# SixAx.net
KiCad netlist of a schematic drawn in Altium Designer
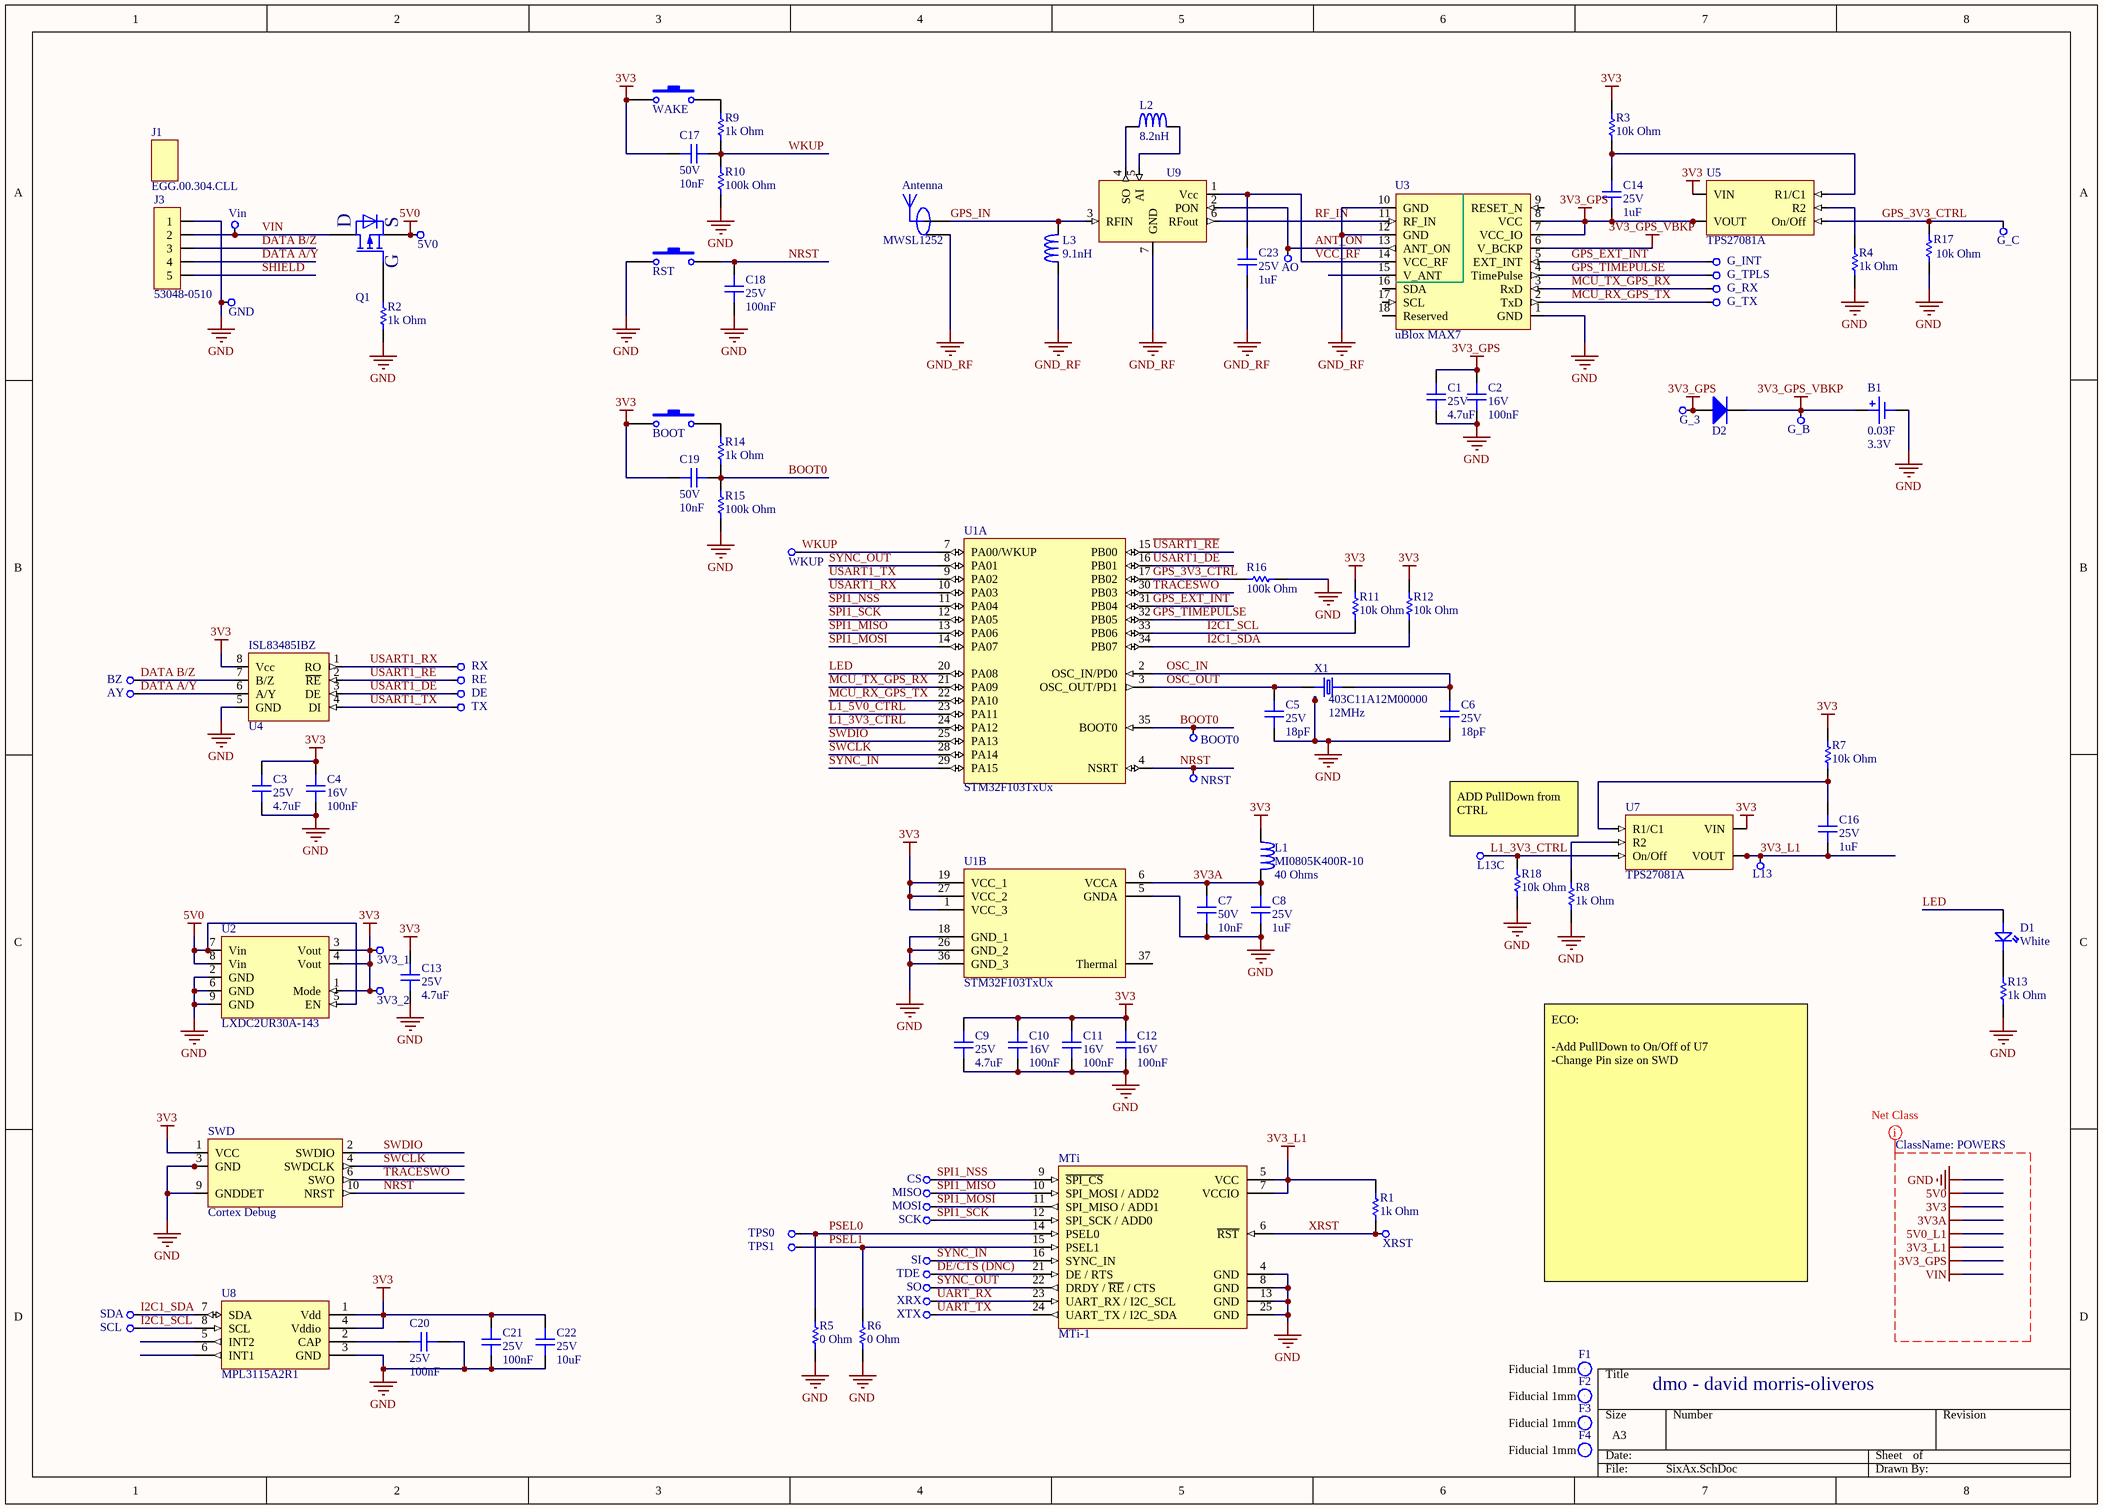
[diagram p0: SixAx.SchDoc]

(export (version "E")
  (design (tool "Eeschema 10.0.6"))
  (components
    (comp (ref "3V3_1")
      (value "TEST")
      (footprint "TEST_1.0mm, SMD")
      (libsource (lib "NaniBox_Conn") (part "TEST"))
    )
    (comp (ref "3V3_2")
      (value "TEST")
      (footprint "TEST_1.0mm, SMD")
      (libsource (lib "NaniBox_Conn") (part "TEST"))
    )
    (comp (ref "5V0")
      (value "TEST")
      (footprint "TEST_1.0mm, SMD")
      (libsource (lib "NaniBox_Conn") (part "TEST"))
    )
    (comp (ref "Antenna")
      (value "MWSL1252")
      (footprint "MWSL1252 - Vertical - SMALLER")
      (description "GPS Antenna, Passive, SMD")
      (fields (field (name "MANUFACTURER") "Maruwa"))
      (libsource (lib "NaniBox_Conn") (part "MWSL1252"))
    )
    (comp (ref "AO")
      (value "TEST")
      (footprint "TEST_0.5mm, SMD")
      (libsource (lib "NaniBox_Conn") (part "TEST"))
    )
    (comp (ref "AY")
      (value "TEST")
      (footprint "TEST_0.5mm, SMD")
      (libsource (lib "NaniBox_Conn") (part "TEST"))
    )
    (comp (ref "B1")
      (value "0.03F")
      (footprint "PAS409HR-VE5R")
      (description "Super Cap, 3.3V, 0.03F")
      (fields
        (field (name "MANUFACTURER") "Taiyo Yuden")
        (field (name "MANUFACTURER PART NUMBER") "PAS409HR-VE5R")
        (field (name "VOLTAGE") "3.3V")
      )
      (libsource (lib "NaniBox") (part "PAS409HR-VE5R"))
    )
    (comp (ref "BOOT")
      (value "TL1015AF160QG")
      (footprint "TL1015AF160QG")
      (description "Switch, Tactile, SMD")
      (fields (field (name "MANUFACTURER") "E-Switch"))
      (libsource (lib "NaniBox") (part "TL1015AF160QG"))
    )
    (comp (ref "BOOT0")
      (value "TEST")
      (footprint "TEST_0.5mm, SMD")
      (libsource (lib "NaniBox_Conn") (part "TEST"))
    )
    (comp (ref "BZ")
      (value "TEST")
      (footprint "TEST_0.5mm, SMD")
      (libsource (lib "NaniBox_Conn") (part "TEST"))
    )
    (comp (ref "C1")
      (value "4.7uF")
      (footprint "CAP 0805")
      (description "MLCC, 4.7uF, 0805, 10%, 25V, X5R")
      (fields
        (field (name "MANUFACTURER") "Samsung")
        (field (name "MANUFACTURER PART NUMBER") "CL21A475KAQNNNE")
        (field (name "VOLTAGE RATING") "25V")
      )
      (libsource (lib "NaniBox") (part "CL21A475KAQNNNE"))
    )
    (comp (ref "C2")
      (value "100nF")
      (footprint "CAP 0402")
      (description "MLCC, 100nF, 0402, 10%, 16V, X7R")
      (fields
        (field (name "MANUFACTURER") "Samsung")
        (field (name "MANUFACTURER PART NUMBER") "CL05B104KO5NNNC")
        (field (name "VOLTAGE RATING") "16V")
      )
      (libsource (lib "NaniBox") (part "CL05B104KO5NNNC"))
    )
    (comp (ref "C3")
      (value "4.7uF")
      (footprint "CAP 0805")
      (description "MLCC, 4.7uF, 0805, 10%, 25V, X5R")
      (fields
        (field (name "MANUFACTURER") "Samsung")
        (field (name "MANUFACTURER PART NUMBER") "CL21A475KAQNNNE")
        (field (name "VOLTAGE RATING") "25V")
      )
      (libsource (lib "NaniBox") (part "CL21A475KAQNNNE"))
    )
    (comp (ref "C4")
      (value "100nF")
      (footprint "CAP 0402")
      (description "MLCC, 100nF, 0402, 10%, 16V, X7R")
      (fields
        (field (name "MANUFACTURER") "Samsung")
        (field (name "MANUFACTURER PART NUMBER") "CL05B104KO5NNNC")
        (field (name "VOLTAGE RATING") "16V")
      )
      (libsource (lib "NaniBox") (part "CL05B104KO5NNNC"))
    )
    (comp (ref "C5")
      (value "18pF")
      (footprint "CAP 0402")
      (description "MLCC, 18pF, 0402, 5%, 25V, C0G")
      (fields
        (field (name "MANUFACTURER") "muRata")
        (field (name "MANUFACTURER PART NUMBER") "GRM1555C1E180JA01D")
        (field (name "VOLTAGE RATING") "25V")
      )
      (libsource (lib "NaniBox") (part "GRM1555C1E180JA01D"))
    )
    (comp (ref "C6")
      (value "18pF")
      (footprint "CAP 0402")
      (description "MLCC, 18pF, 0402, 5%, 25V, C0G")
      (fields
        (field (name "MANUFACTURER") "muRata")
        (field (name "MANUFACTURER PART NUMBER") "GRM1555C1E180JA01D")
        (field (name "VOLTAGE RATING") "25V")
      )
      (libsource (lib "NaniBox") (part "GRM1555C1E180JA01D"))
    )
    (comp (ref "C7")
      (value "10nF")
      (footprint "CAP 0402")
      (description "MLCC, 10nF, 0402, 10%, 50V, X7R")
      (fields
        (field (name "MANUFACTURER") "Samsung")
        (field (name "MANUFACTURER PART NUMBER") "CL05B103KB5NNNC")
        (field (name "VOLTAGE RATING") "50V")
      )
      (libsource (lib "NaniBox") (part "CL05B103KB5NNNC"))
    )
    (comp (ref "C8")
      (value "1uF")
      (footprint "CAP 0603")
      (description "MLCC, 1uF, 0603, 10%, 25V")
      (fields
        (field (name "MANUFACTURER") "Taiyo Yuden")
        (field (name "MANUFACTURER PART NUMBER") "TMK107B7105KA-T")
        (field (name "VOLTAGE RATING") "25V")
      )
      (libsource (lib "NaniBox") (part "TMK107B7105KA-T"))
    )
    (comp (ref "C9")
      (value "4.7uF")
      (footprint "CAP 0805")
      (description "MLCC, 4.7uF, 0805, 10%, 25V, X5R")
      (fields
        (field (name "MANUFACTURER") "Samsung")
        (field (name "MANUFACTURER PART NUMBER") "CL21A475KAQNNNE")
        (field (name "VOLTAGE RATING") "25V")
      )
      (libsource (lib "NaniBox") (part "CL21A475KAQNNNE"))
    )
    (comp (ref "C10")
      (value "100nF")
      (footprint "CAP 0402")
      (description "MLCC, 100nF, 0402, 10%, 16V, X7R")
      (fields
        (field (name "MANUFACTURER") "Samsung")
        (field (name "MANUFACTURER PART NUMBER") "CL05B104KO5NNNC")
        (field (name "VOLTAGE RATING") "16V")
      )
      (libsource (lib "NaniBox") (part "CL05B104KO5NNNC"))
    )
    (comp (ref "C11")
      (value "100nF")
      (footprint "CAP 0402")
      (description "MLCC, 100nF, 0402, 10%, 16V, X7R")
      (fields
        (field (name "MANUFACTURER") "Samsung")
        (field (name "MANUFACTURER PART NUMBER") "CL05B104KO5NNNC")
        (field (name "VOLTAGE RATING") "16V")
      )
      (libsource (lib "NaniBox") (part "CL05B104KO5NNNC"))
    )
    (comp (ref "C12")
      (value "100nF")
      (footprint "CAP 0402")
      (description "MLCC, 100nF, 0402, 10%, 16V, X7R")
      (fields
        (field (name "MANUFACTURER") "Samsung")
        (field (name "MANUFACTURER PART NUMBER") "CL05B104KO5NNNC")
        (field (name "VOLTAGE RATING") "16V")
      )
      (libsource (lib "NaniBox") (part "CL05B104KO5NNNC"))
    )
    (comp (ref "C13")
      (value "4.7uF")
      (footprint "CAP 0805")
      (description "MLCC, 4.7uF, 0805, 10%, 25V, X5R")
      (fields
        (field (name "MANUFACTURER") "Samsung")
        (field (name "MANUFACTURER PART NUMBER") "CL21A475KAQNNNE")
        (field (name "VOLTAGE RATING") "25V")
      )
      (libsource (lib "NaniBox") (part "CL21A475KAQNNNE"))
    )
    (comp (ref "C14")
      (value "1uF")
      (footprint "CAP 0603")
      (description "MLCC, 1uF, 0603, 10%, 25V, X5R")
      (fields
        (field (name "MANUFACTURER") "Samsung")
        (field (name "MANUFACTURER PART NUMBER") "CL10A105KA8NNNC")
        (field (name "VOLTAGE RATING") "25V")
      )
      (libsource (lib "NaniBox") (part "CL10A105KA8NNNC"))
    )
    (comp (ref "C16")
      (value "1uF")
      (footprint "CAP 0603")
      (description "MLCC, 1uF, 0603, 10%, 25V, X5R")
      (fields
        (field (name "MANUFACTURER") "Samsung")
        (field (name "MANUFACTURER PART NUMBER") "CL10A105KA8NNNC")
        (field (name "VOLTAGE RATING") "25V")
      )
      (libsource (lib "NaniBox") (part "CL10A105KA8NNNC"))
    )
    (comp (ref "C17")
      (value "10nF")
      (footprint "CAP 0402")
      (description "MLCC, 10nF, 0402, 10%, 50V, X7R")
      (fields
        (field (name "MANUFACTURER") "Samsung")
        (field (name "MANUFACTURER PART NUMBER") "CL05B103KB5NNNC")
        (field (name "VOLTAGE RATING") "50V")
      )
      (libsource (lib "NaniBox") (part "CL05B103KB5NNNC"))
    )
    (comp (ref "C18")
      (value "100nF")
      (footprint "CAP 0402")
      (description "MLCC, 100nF, 0402, 10%, 25V, X5R")
      (fields
        (field (name "MANUFACTURER") "Samsung")
        (field (name "MANUFACTURER PART NUMBER") "CL05A104KA5NNNC")
        (field (name "VOLTAGE RATING") "25V")
      )
      (libsource (lib "NaniBox") (part "CL05A104KA5NNNC"))
    )
    (comp (ref "C19")
      (value "10nF")
      (footprint "CAP 0402")
      (description "MLCC, 10nF, 0402, 10%, 50V, X7R")
      (fields
        (field (name "MANUFACTURER") "Samsung")
        (field (name "MANUFACTURER PART NUMBER") "CL05B103KB5NNNC")
        (field (name "VOLTAGE RATING") "50V")
      )
      (libsource (lib "NaniBox") (part "CL05B103KB5NNNC"))
    )
    (comp (ref "C20")
      (value "100nF")
      (footprint "CAP 0402")
      (description "MLCC, 100nF, 0402, 10%, 25V, X5R")
      (fields
        (field (name "MANUFACTURER") "Samsung")
        (field (name "MANUFACTURER PART NUMBER") "CL05A104KA5NNNC")
        (field (name "VOLTAGE RATING") "25V")
      )
      (libsource (lib "NaniBox") (part "CL05A104KA5NNNC"))
    )
    (comp (ref "C21")
      (value "100nF")
      (footprint "CAP 0402")
      (description "MLCC, 100nF, 0402, 10%, 25V, X5R")
      (fields
        (field (name "MANUFACTURER") "Samsung")
        (field (name "MANUFACTURER PART NUMBER") "CL05A104KA5NNNC")
        (field (name "VOLTAGE RATING") "25V")
      )
      (libsource (lib "NaniBox") (part "CL05A104KA5NNNC"))
    )
    (comp (ref "C22")
      (value "10uF")
      (footprint "CAP 0805")
      (description "MLCC, 10uF, 0805, 10%, 25V, X5R")
      (fields
        (field (name "MANUFACTURER") "Samsung")
        (field (name "MANUFACTURER PART NUMBER") "CL21A106KAYNNNE")
        (field (name "VOLTAGE RATING") "25V")
      )
      (libsource (lib "NaniBox") (part "CL21A106KAYNNNE"))
    )
    (comp (ref "C23")
      (value "1uF")
      (footprint "CAP 0603")
      (description "MLCC, 1uF, 0603, 10%, 25V, X5R")
      (fields
        (field (name "MANUFACTURER") "Samsung")
        (field (name "MANUFACTURER PART NUMBER") "CL10A105KA8NNNC")
        (field (name "VOLTAGE RATING") "25V")
      )
      (libsource (lib "NaniBox") (part "CL10A105KA8NNNC"))
    )
    (comp (ref "CS")
      (value "TEST")
      (footprint "TEST_0.5mm, SMD")
      (libsource (lib "NaniBox_Conn") (part "TEST"))
    )
    (comp (ref "D1")
      (value "White")
      (footprint "LED 0603")
      (description "LED, White, 0603")
      (fields (field (name "MANUFACTURER PART NUMBER") "1608SWD-04"))
      (libsource (lib "NaniBox") (part "1608SWD-04"))
    )
    (comp (ref "D2")
      (value "CDSQR400B")
      (footprint "SOD-923F")
      (description "DIODE, Switching, Low Leakage, 90V, 100mA")
      (fields (field (name "MANUFACTURER") "Comchip Technology"))
      (libsource (lib "NaniBox") (part "CDSQR400B"))
    )
    (comp (ref "DE")
      (value "TEST")
      (footprint "TEST_0.5mm, SMD")
      (libsource (lib "NaniBox_Conn") (part "TEST"))
    )
    (comp (ref "F1")
      (value "~")
      (footprint "Fiducial_1mm")
      (libsource (lib "NaniBox_Conn") (part "Fiducial 1mm"))
    )
    (comp (ref "F2")
      (value "~")
      (footprint "Fiducial_1mm")
      (libsource (lib "NaniBox_Conn") (part "Fiducial 1mm"))
    )
    (comp (ref "F3")
      (value "~")
      (footprint "Fiducial_1mm")
      (libsource (lib "NaniBox_Conn") (part "Fiducial 1mm"))
    )
    (comp (ref "F4")
      (value "~")
      (footprint "Fiducial_1mm")
      (libsource (lib "NaniBox_Conn") (part "Fiducial 1mm"))
    )
    (comp (ref "GND")
      (value "TEST")
      (footprint "TEST_1.0mm, SMD")
      (libsource (lib "NaniBox_Conn") (part "TEST"))
    )
    (comp (ref "G_3")
      (value "TEST")
      (footprint "TEST_0.5mm, SMD")
      (libsource (lib "NaniBox_Conn") (part "TEST"))
    )
    (comp (ref "G_B")
      (value "TEST")
      (footprint "TEST_0.5mm, SMD")
      (libsource (lib "NaniBox_Conn") (part "TEST"))
    )
    (comp (ref "G_C")
      (value "TEST")
      (footprint "TEST_0.5mm, SMD")
      (libsource (lib "NaniBox_Conn") (part "TEST"))
    )
    (comp (ref "G_INT")
      (value "TEST")
      (footprint "TEST_0.5mm, SMD")
      (libsource (lib "NaniBox_Conn") (part "TEST"))
    )
    (comp (ref "G_RX")
      (value "TEST")
      (footprint "TEST_0.5mm, SMD")
      (libsource (lib "NaniBox_Conn") (part "TEST"))
    )
    (comp (ref "G_TPLS")
      (value "TEST")
      (footprint "TEST_0.5mm, SMD")
      (libsource (lib "NaniBox_Conn") (part "TEST"))
    )
    (comp (ref "G_TX")
      (value "TEST")
      (footprint "TEST_0.5mm, SMD")
      (libsource (lib "NaniBox_Conn") (part "TEST"))
    )
    (comp (ref "J1")
      (value "EGG.00.304.CLL")
      (footprint "EGG.00.304.CLL")
      (description "LEMO 00, 4-pin")
      (libsource (lib "NaniBox") (part "EGG.00.304.CLL"))
    )
    (comp (ref "J3")
      (value "53048-0510")
      (footprint "PicoBlade, 53048-0510")
      (description "PicoBlade, Header, R/A, PTH, 5 Pos, 1.25mm Pitch")
      (fields (field (name "MANUFACTURER") "Molex"))
      (libsource (lib "NaniBox_Conn") (part "53048-0510"))
    )
    (comp (ref "L1")
      (value "MI0805K400R-10")
      (footprint "IND 0805")
      (description "IND, EMI, 40Ohm, 100MHz, 1.5A, 0805")
      (fields (field (name "MANUFACTURER") "Laird") (field (name "IMPEDENCE") "40 Ohms"))
      (libsource (lib "NaniBox") (part "MI0805K400R-10"))
    )
    (comp (ref "L2")
      (value "8.2nH")
      (footprint "IND 0402")
      (description "IND, 8.2nH, 5%, 100MHz")
      (fields
        (field (name "MANUFACTURER") "Murata Electronics")
        (field (name "MANUFACTURER PART NUMBER") "LQW15AN8N2J00D")
      )
      (libsource (lib "NaniBox") (part "LQW15AN8N2J00D"))
    )
    (comp (ref "L3")
      (value "9.1nH")
      (footprint "IND 0402")
      (description "IND, 9.1nH, 5%, 100MHz")
      (fields
        (field (name "MANUFACTURER") "Murata Electronics")
        (field (name "MANUFACTURER PART NUMBER") "LQW15AN9N1J00D")
      )
      (libsource (lib "NaniBox") (part "LQW15AN9N1J00D"))
    )
    (comp (ref "L13")
      (value "TEST")
      (footprint "TEST_0.5mm, SMD")
      (libsource (lib "NaniBox_Conn") (part "TEST"))
    )
    (comp (ref "L13C")
      (value "TEST")
      (footprint "TEST_0.5mm, SMD")
      (libsource (lib "NaniBox_Conn") (part "TEST"))
    )
    (comp (ref "MISO")
      (value "TEST")
      (footprint "TEST_0.5mm, SMD")
      (libsource (lib "NaniBox_Conn") (part "TEST"))
    )
    (comp (ref "MOSI")
      (value "TEST")
      (footprint "TEST_0.5mm, SMD")
      (libsource (lib "NaniBox_Conn") (part "TEST"))
    )
    (comp (ref "MTi")
      (value "MTi-1")
      (footprint "PLCC28 - XSens MTi-1 Special")
      (description "XSens MTi-1 Series")
      (fields (field (name "MANUFACTURER") "XSens"))
      (libsource (lib "NaniBox") (part "MTi-1"))
    )
    (comp (ref "NRST")
      (value "TEST")
      (footprint "TEST_0.5mm, SMD")
      (libsource (lib "NaniBox_Conn") (part "TEST"))
    )
    (comp (ref "Q1")
      (value "PMV48XP,215")
      (footprint "SOT23-3")
      (description "MOSFET P-CH -20 V -3.5 A, SOT23-3")
      (fields (field (name "MANUFACTURER") "NXP"))
      (libsource (lib "NaniBox") (part "PMV48XP,215"))
    )
    (comp (ref "R1")
      (value "1k Ohm")
      (footprint "RES 0402")
      (description "RES, 0402, 1k, 1%")
      (fields (field (name "TOLERANCE") "1%") (field (name "MANUFACTURER") "Yageo"))
      (libsource (lib "NaniBox") (part "P311-1.00KLRTR-ND"))
    )
    (comp (ref "R2")
      (value "1k Ohm")
      (footprint "RES 0402")
      (description "RES, 0402, 1k, 1%")
      (fields (field (name "TOLERANCE") "1%") (field (name "MANUFACTURER") "Yageo"))
      (libsource (lib "NaniBox") (part "P311-1.00KLRTR-ND"))
    )
    (comp (ref "R3")
      (value "10k Ohm")
      (footprint "RES 0402")
      (description "RES, 0402, 10k, 1%")
      (fields (field (name "TOLERANCE") "1%") (field (name "MANUFACTURER") "Yageo"))
      (libsource (lib "NaniBox") (part "P311-10.0KLRTR-ND"))
    )
    (comp (ref "R4")
      (value "1k Ohm")
      (footprint "RES 0402")
      (description "RES, 0402, 1k, 1%")
      (fields (field (name "TOLERANCE") "1%") (field (name "MANUFACTURER") "Yageo"))
      (libsource (lib "NaniBox") (part "P311-1.00KLRTR-ND"))
    )
    (comp (ref "R5")
      (value "0 Ohm")
      (footprint "RES 0402")
      (description "RES, 0402, 0, 5%")
      (fields (field (name "TOLERANCE") "5%") (field (name "MANUFACTURER") "Yageo"))
      (libsource (lib "NaniBox") (part "P311-0.0JRTR-ND"))
    )
    (comp (ref "R6")
      (value "0 Ohm")
      (footprint "RES 0402")
      (description "RES, 0402, 0, 5%")
      (fields (field (name "TOLERANCE") "5%") (field (name "MANUFACTURER") "Yageo"))
      (libsource (lib "NaniBox") (part "P311-0.0JRTR-ND"))
    )
    (comp (ref "R7")
      (value "10k Ohm")
      (footprint "RES 0402")
      (description "RES, 0402, 10k, 1%")
      (fields (field (name "TOLERANCE") "1%") (field (name "MANUFACTURER") "Yageo"))
      (libsource (lib "NaniBox") (part "P311-10.0KLRTR-ND"))
    )
    (comp (ref "R8")
      (value "1k Ohm")
      (footprint "RES 0402")
      (description "RES, 0402, 1k, 1%")
      (fields (field (name "TOLERANCE") "1%") (field (name "MANUFACTURER") "Yageo"))
      (libsource (lib "NaniBox") (part "P311-1.00KLRTR-ND"))
    )
    (comp (ref "R9")
      (value "1k Ohm")
      (footprint "RES 0402")
      (description "RES, 0402, 1k, 1%")
      (fields (field (name "TOLERANCE") "1%") (field (name "MANUFACTURER") "Yageo"))
      (libsource (lib "NaniBox") (part "P311-1.00KLRTR-ND"))
    )
    (comp (ref "R10")
      (value "100k Ohm")
      (footprint "RES 0402")
      (description "RES, 0402, 100k, 1%")
      (fields (field (name "TOLERANCE") "1%") (field (name "MANUFACTURER") "Yageo"))
      (libsource (lib "NaniBox") (part "P311-100KLRTR-ND"))
    )
    (comp (ref "R11")
      (value "10k Ohm")
      (footprint "RES 0402")
      (description "RES, 0402, 10k, 1%")
      (fields (field (name "TOLERANCE") "1%") (field (name "MANUFACTURER") "Yageo"))
      (libsource (lib "NaniBox") (part "P311-10.0KLRTR-ND"))
    )
    (comp (ref "R12")
      (value "10k Ohm")
      (footprint "RES 0402")
      (description "RES, 0402, 10k, 1%")
      (fields (field (name "TOLERANCE") "1%") (field (name "MANUFACTURER") "Yageo"))
      (libsource (lib "NaniBox") (part "P311-10.0KLRTR-ND"))
    )
    (comp (ref "R13")
      (value "1k Ohm")
      (footprint "RES 0402")
      (description "RES, 0402, 1k, 1%")
      (fields (field (name "TOLERANCE") "1%") (field (name "MANUFACTURER") "Yageo"))
      (libsource (lib "NaniBox") (part "P311-1.00KLRTR-ND"))
    )
    (comp (ref "R14")
      (value "1k Ohm")
      (footprint "RES 0402")
      (description "RES, 0402, 1k, 1%")
      (fields (field (name "TOLERANCE") "1%") (field (name "MANUFACTURER") "Yageo"))
      (libsource (lib "NaniBox") (part "P311-1.00KLRTR-ND"))
    )
    (comp (ref "R15")
      (value "100k Ohm")
      (footprint "RES 0402")
      (description "RES, 0402, 100k, 1%")
      (fields (field (name "TOLERANCE") "1%") (field (name "MANUFACTURER") "Yageo"))
      (libsource (lib "NaniBox") (part "P311-100KLRTR-ND"))
    )
    (comp (ref "R16")
      (value "100k Ohm")
      (footprint "RES 0402")
      (description "RES, 0402, 100k, 1%")
      (fields (field (name "TOLERANCE") "1%") (field (name "MANUFACTURER") "Yageo"))
      (libsource (lib "NaniBox") (part "P311-100KLRTR-ND"))
    )
    (comp (ref "R17")
      (value "10k Ohm")
      (footprint "RES 0402")
      (description "RES, 0402, 10k, 1%")
      (fields (field (name "TOLERANCE") "1%") (field (name "MANUFACTURER") "Yageo"))
      (libsource (lib "NaniBox") (part "P311-10.0KLRTR-ND"))
    )
    (comp (ref "R18")
      (value "10k Ohm")
      (footprint "RES 0402")
      (description "RES, 0402, 10k, 1%")
      (fields (field (name "TOLERANCE") "1%") (field (name "MANUFACTURER") "Yageo"))
      (libsource (lib "NaniBox") (part "P311-10.0KLRTR-ND"))
    )
    (comp (ref "RE")
      (value "TEST")
      (footprint "TEST_0.5mm, SMD")
      (libsource (lib "NaniBox_Conn") (part "TEST"))
    )
    (comp (ref "RST")
      (value "TL1015AF160QG")
      (footprint "TL1015AF160QG")
      (description "Switch, Tactile, SMD")
      (fields (field (name "MANUFACTURER") "E-Switch"))
      (libsource (lib "NaniBox") (part "TL1015AF160QG"))
    )
    (comp (ref "RX")
      (value "TEST")
      (footprint "TEST_0.5mm, SMD")
      (libsource (lib "NaniBox_Conn") (part "TEST"))
    )
    (comp (ref "SCK")
      (value "TEST")
      (footprint "TEST_0.5mm, SMD")
      (libsource (lib "NaniBox_Conn") (part "TEST"))
    )
    (comp (ref "SCL")
      (value "TEST")
      (footprint "TEST_0.5mm, SMD")
      (libsource (lib "NaniBox_Conn") (part "TEST"))
    )
    (comp (ref "SDA")
      (value "TEST")
      (footprint "TEST_0.5mm, SMD")
      (libsource (lib "NaniBox_Conn") (part "TEST"))
    )
    (comp (ref "SI")
      (value "TEST")
      (footprint "TEST_0.5mm, SMD")
      (libsource (lib "NaniBox_Conn") (part "TEST"))
    )
    (comp (ref "SO")
      (value "TEST")
      (footprint "TEST_0.5mm, SMD")
      (libsource (lib "NaniBox_Conn") (part "TEST"))
    )
    (comp (ref "SWD")
      (value "CORTEX_DEBUG")
      (footprint "H_05x02 - 1.27mm")
      (description "Cortex Debug")
      (fields (field (name "MANUFACTURER PART NUMBER") "Cortex Debug"))
      (libsource (lib "NaniBox") (part "CORTEX_DEBUG"))
    )
    (comp (ref "TDE")
      (value "TEST")
      (footprint "TEST_0.5mm, SMD")
      (libsource (lib "NaniBox_Conn") (part "TEST"))
    )
    (comp (ref "TPS0")
      (value "TEST")
      (footprint "TEST_0.5mm, SMD")
      (libsource (lib "NaniBox_Conn") (part "TEST"))
    )
    (comp (ref "TPS1")
      (value "TEST")
      (footprint "TEST_0.5mm, SMD")
      (libsource (lib "NaniBox_Conn") (part "TEST"))
    )
    (comp (ref "TX")
      (value "TEST")
      (footprint "TEST_0.5mm, SMD")
      (libsource (lib "NaniBox_Conn") (part "TEST"))
    )
    (comp (ref "U1")
      (value "STM32F103TxUx")
      (footprint "QFN36 - 0.5mm - NO THERMAL VIAS")
      (description "MCU, ARM-based 32-bit MCU with 64  or 128 KB Flash, USB, CAN, 7 timers, 2 ADCs, 9 com. interfaces")
      (libsource (lib "NaniBox") (part "STM32F103TxUx"))
    )
    (comp (ref "U2")
      (value "LXDC2UR30A-143")
      (footprint "BGA - 9 - LXDC2UR")
      (description "DC-DC 3.0Vout 600mA 2.5x2.3mm uDCDC")
      (libsource (lib "NaniBox") (part "LXDC2UR30A-143"))
    )
    (comp (ref "U3")
      (value "uBlox MAX7")
      (footprint "uBlox MAX7")
      (description "GPS, u-blox 7 GPS/GNSS module")
      (libsource (lib "NaniBox") (part "uBlox MAX7"))
    )
    (comp (ref "U4")
      (value "ISL83485IBZ")
      (footprint "SOIC8")
      (description "RS-422/RS-485, 3.3V, HalfDuplex, TRN 1TX/1RX, W/SHTDN")
      (fields (field (name "MANUFACTURER") "Intersil"))
      (libsource (lib "NaniBox") (part "ISL83485IBZ"))
    )
    (comp (ref "U5")
      (value "TPS27081ADDCR")
      (footprint "SOT23-6")
      (description "High Side Load Switch PFET 1.2V-8V 3A")
      (fields
        (field (name "MANUFACTURER") "TI")
        (field (name "MANUFACTURER PART NUMBER - SIMPLE") "TPS27081A")
      )
      (libsource (lib "NaniBox") (part "TPS27081ADDCR"))
    )
    (comp (ref "U7")
      (value "TPS27081ADDCR")
      (footprint "SOT23-6")
      (description "High Side Load Switch PFET 1.2V-8V 3A")
      (fields
        (field (name "MANUFACTURER") "TI")
        (field (name "MANUFACTURER PART NUMBER - SIMPLE") "TPS27081A")
      )
      (libsource (lib "") (part "TPS27081ADDCR_1"))
    )
    (comp (ref "U8")
      (value "MPL3115A2R1")
      (footprint "MPL3115A2R1")
      (description "Barometric Pressure Sensor, SMD")
      (fields (field (name "MANUFACTURER") "Freescale"))
      (libsource (lib "NaniBox") (part "MPL3115A2R1"))
    )
    (comp (ref "U9")
      (value "BGM1043N7")
      (footprint "TSNP-7-10")
      (description "RF, LNA, GPS")
      (fields (field (name "MANUFACTURER") "Infineon"))
      (libsource (lib "NaniBox") (part "BGM1043N7"))
    )
    (comp (ref "Vin")
      (value "TEST")
      (footprint "TEST_1.0mm, SMD")
      (libsource (lib "NaniBox_Conn") (part "TEST"))
    )
    (comp (ref "WAKE")
      (value "EVQ-P44B3M")
      (footprint "EVQ-P44B3M - No Corner Holes")
      (description "Switch, Tactile, Right Angle, Mid-Plane Mount,, SMD")
      (fields (field (name "MANUFACTURER") "E-Switch"))
      (libsource (lib "NaniBox") (part "EVQ-P44B3M"))
    )
    (comp (ref "WKUP")
      (value "TEST")
      (footprint "TEST_0.5mm, SMD")
      (libsource (lib "NaniBox_Conn") (part "TEST"))
    )
    (comp (ref "X1")
      (value "403C11A12M00000")
      (footprint "XTAL_3.2x2.5")
      (description "Crystal 12MHz 10pF 10ppm 3.2x2.5mm")
      (fields (field (name "FREQUENCY") "12MHz") (field (name "MANUFACTURER") "CTS Electronic Components"))
      (libsource (lib "NaniBox") (part "403C11A12M00000"))
    )
    (comp (ref "XRST")
      (value "TEST")
      (footprint "TEST_0.5mm, SMD")
      (libsource (lib "NaniBox_Conn") (part "TEST"))
    )
    (comp (ref "XRX")
      (value "TEST")
      (footprint "TEST_0.5mm, SMD")
      (libsource (lib "NaniBox_Conn") (part "TEST"))
    )
    (comp (ref "XTX")
      (value "TEST")
      (footprint "TEST_0.5mm, SMD")
      (libsource (lib "NaniBox_Conn") (part "TEST"))
    )
  )
  (nets
    (net (code "1") (name "/ANT_ON") (class "Default")
      (node (ref "AO") (pin "0") (pinfunction "0_0") (pintype "passive"))
      (node (ref "U3") (pin "13") (pinfunction "ANT_ON_13") (pintype "output"))
      (node (ref "U9") (pin "2") (pinfunction "PON_2") (pintype "input"))
    )
    (net (code "2") (name "/BOOT0") (class "Default")
      (node (ref "BOOT0") (pin "0") (pinfunction "0_0") (pintype "passive"))
      (node (ref "C19") (pin "2") (pinfunction "2_2") (pintype "passive"))
      (node (ref "R14") (pin "1") (pinfunction "1_1") (pintype "passive"))
      (node (ref "R15") (pin "2") (pinfunction "2_2") (pintype "passive"))
      (node (ref "U1") (pin "35") (pinfunction "BOOT0_35") (pintype "input"))
    )
    (net (code "3") (name "/DATA A{slash}Y") (class "Default")
      (node (ref "AY") (pin "0") (pinfunction "0_0") (pintype "passive"))
      (node (ref "J3") (pin "4") (pinfunction "4_4") (pintype "passive"))
      (node (ref "U4") (pin "6") (pinfunction "A/Y_6") (pintype "bidirectional"))
    )
    (net (code "4") (name "/DATA B{slash}Z") (class "Default")
      (node (ref "BZ") (pin "0") (pinfunction "0_0") (pintype "passive"))
      (node (ref "J3") (pin "3") (pinfunction "3_3") (pintype "passive"))
      (node (ref "U4") (pin "7") (pinfunction "B/Z_7") (pintype "bidirectional"))
    )
    (net (code "5") (name "/DE{slash}CTS (DNC)") (class "Default")
      (node (ref "MTi") (pin "21") (pinfunction "DE_/_RTS_21") (pintype "input"))
      (node (ref "TDE") (pin "0") (pinfunction "0_0") (pintype "passive"))
    )
    (net (code "6") (name "/GPS_3V3_CTRL") (class "Default")
      (node (ref "G_C") (pin "0") (pinfunction "0_0") (pintype "passive"))
      (node (ref "R16") (pin "1") (pinfunction "1_1") (pintype "passive"))
      (node (ref "R17") (pin "2") (pinfunction "2_2") (pintype "passive"))
      (node (ref "U1") (pin "17") (pinfunction "PB02_17") (pintype "bidirectional"))
      (node (ref "U5") (pin "5") (pinfunction "On/Off_5") (pintype "input"))
    )
    (net (code "7") (name "/GPS_EXT_INT") (class "Default")
      (node (ref "G_INT") (pin "0") (pinfunction "0_0") (pintype "passive"))
      (node (ref "U1") (pin "31") (pinfunction "PB04_31") (pintype "bidirectional"))
      (node (ref "U3") (pin "5") (pinfunction "EXT_INT_5") (pintype "input"))
    )
    (net (code "8") (name "/GPS_IN") (class "Default")
      (node (ref "Antenna") (pin "SIG") (pinfunction "SIG_SIG") (pintype "passive"))
      (node (ref "L3") (pin "2") (pinfunction "2_2") (pintype "passive"))
      (node (ref "U9") (pin "3") (pinfunction "RFIN_3") (pintype "input"))
    )
    (net (code "9") (name "/GPS_TIMEPULSE") (class "Default")
      (node (ref "G_TPLS") (pin "0") (pinfunction "0_0") (pintype "passive"))
      (node (ref "U1") (pin "32") (pinfunction "PB05_32") (pintype "bidirectional"))
      (node (ref "U3") (pin "4") (pinfunction "TimePulse_4") (pintype "output"))
    )
    (net (code "10") (name "/I2C1_SCL") (class "Default")
      (node (ref "R11") (pin "1") (pinfunction "1_1") (pintype "passive"))
      (node (ref "SCL") (pin "0") (pinfunction "0_0") (pintype "passive"))
      (node (ref "U1") (pin "33") (pinfunction "PB06_33") (pintype "bidirectional"))
      (node (ref "U8") (pin "8") (pinfunction "SCL_8") (pintype "input"))
    )
    (net (code "11") (name "/I2C1_SDA") (class "Default")
      (node (ref "R12") (pin "1") (pinfunction "1_1") (pintype "passive"))
      (node (ref "SDA") (pin "0") (pinfunction "0_0") (pintype "passive"))
      (node (ref "U1") (pin "34") (pinfunction "PB07_34") (pintype "bidirectional"))
      (node (ref "U8") (pin "7") (pinfunction "SDA_7") (pintype "bidirectional"))
    )
    (net (code "12") (name "/L1_3V3_CTRL") (class "Default")
      (node (ref "L13C") (pin "0") (pinfunction "0_0") (pintype "passive"))
      (node (ref "R18") (pin "2") (pinfunction "2_2") (pintype "passive"))
      (node (ref "U1") (pin "24") (pinfunction "PA12_24") (pintype "bidirectional"))
      (node (ref "U7") (pin "5") (pinfunction "On/Off_5") (pintype "input"))
    )
    (net (code "13") (name "/L1_5V0_CTRL") (class "Default")
      (node (ref "U1") (pin "23") (pinfunction "PA11_23") (pintype "bidirectional"))
    )
    (net (code "14") (name "/LED") (class "Default")
      (node (ref "D1") (pin "A") (pinfunction "A_A") (pintype "power_in"))
      (node (ref "U1") (pin "20") (pinfunction "PA08_20") (pintype "bidirectional"))
    )
    (net (code "15") (name "/MCU_RX_GPS_TX") (class "Default")
      (node (ref "G_TX") (pin "0") (pinfunction "0_0") (pintype "passive"))
      (node (ref "U1") (pin "22") (pinfunction "PA10_22") (pintype "bidirectional"))
      (node (ref "U3") (pin "2") (pinfunction "TxD_2") (pintype "output"))
    )
    (net (code "16") (name "/MCU_TX_GPS_RX") (class "Default")
      (node (ref "G_RX") (pin "0") (pinfunction "0_0") (pintype "passive"))
      (node (ref "U1") (pin "21") (pinfunction "PA09_21") (pintype "bidirectional"))
      (node (ref "U3") (pin "3") (pinfunction "RxD_3") (pintype "input"))
    )
    (net (code "17") (name "/NRST") (class "Default")
      (node (ref "C18") (pin "2") (pinfunction "2_2") (pintype "passive"))
      (node (ref "NRST") (pin "0") (pinfunction "0_0") (pintype "passive"))
      (node (ref "RST") (pin "2") (pinfunction "2_2") (pintype "passive"))
      (node (ref "SWD") (pin "10") (pinfunction "NRST_10") (pintype "output"))
      (node (ref "U1") (pin "4") (pinfunction "NSRT_4") (pintype "bidirectional"))
    )
    (net (code "18") (name "/OSC_IN") (class "Default")
      (node (ref "C6") (pin "2") (pinfunction "2_2") (pintype "passive"))
      (node (ref "U1") (pin "2") (pinfunction "OSC_IN/PD0_2") (pintype "input"))
      (node (ref "X1") (pin "3") (pinfunction "3_3") (pintype "passive"))
    )
    (net (code "19") (name "/OSC_OUT") (class "Default")
      (node (ref "C5") (pin "2") (pinfunction "2_2") (pintype "passive"))
      (node (ref "U1") (pin "3") (pinfunction "OSC_OUT/PD1_3") (pintype "output"))
      (node (ref "X1") (pin "1") (pinfunction "1_1") (pintype "passive"))
    )
    (net (code "20") (name "/PSEL0") (class "Default")
      (node (ref "MTi") (pin "14") (pinfunction "PSEL0_14") (pintype "input"))
      (node (ref "R5") (pin "2") (pinfunction "2_2") (pintype "passive"))
      (node (ref "TPS0") (pin "0") (pinfunction "0_0") (pintype "passive"))
    )
    (net (code "21") (name "/PSEL1") (class "Default")
      (node (ref "MTi") (pin "15") (pinfunction "PSEL1_15") (pintype "input"))
      (node (ref "R6") (pin "2") (pinfunction "2_2") (pintype "passive"))
      (node (ref "TPS1") (pin "0") (pinfunction "0_0") (pintype "passive"))
    )
    (net (code "22") (name "/RF_IN") (class "Default")
      (node (ref "U3") (pin "11") (pinfunction "RF_IN_11") (pintype "input"))
      (node (ref "U9") (pin "6") (pinfunction "RFout_6") (pintype "output"))
    )
    (net (code "23") (name "/SHIELD") (class "Default")
      (node (ref "J3") (pin "5") (pinfunction "5_5") (pintype "passive"))
    )
    (net (code "24") (name "/SPI1_MISO") (class "Default")
      (node (ref "MISO") (pin "0") (pinfunction "0_0") (pintype "passive"))
      (node (ref "MTi") (pin "10") (pinfunction "SPI_MOSI_/_ADD2_10") (pintype "input"))
      (node (ref "U1") (pin "13") (pinfunction "PA06_13") (pintype "bidirectional"))
    )
    (net (code "25") (name "/SPI1_MOSI") (class "Default")
      (node (ref "MOSI") (pin "0") (pinfunction "0_0") (pintype "passive"))
      (node (ref "MTi") (pin "11") (pinfunction "SPI_MISO_/_ADD1_11") (pintype "output"))
      (node (ref "U1") (pin "14") (pinfunction "PA07_14") (pintype "bidirectional"))
    )
    (net (code "26") (name "/SPI1_NSS") (class "Default")
      (node (ref "CS") (pin "0") (pinfunction "0_0") (pintype "passive"))
      (node (ref "MTi") (pin "9") (pinfunction "SPI_CS_9") (pintype "input"))
      (node (ref "U1") (pin "11") (pinfunction "PA04_11") (pintype "bidirectional"))
    )
    (net (code "27") (name "/SPI1_SCK") (class "Default")
      (node (ref "MTi") (pin "12") (pinfunction "SPI_SCK_/_ADD0_12") (pintype "input"))
      (node (ref "SCK") (pin "0") (pinfunction "0_0") (pintype "passive"))
      (node (ref "U1") (pin "12") (pinfunction "PA05_12") (pintype "bidirectional"))
    )
    (net (code "28") (name "/SWCLK") (class "Default")
      (node (ref "SWD") (pin "4") (pinfunction "SWDCLK_4") (pintype "output"))
      (node (ref "U1") (pin "28") (pinfunction "PA14_28") (pintype "bidirectional"))
    )
    (net (code "29") (name "/SWDIO") (class "Default")
      (node (ref "SWD") (pin "2") (pinfunction "SWDIO_2") (pintype "bidirectional"))
      (node (ref "U1") (pin "25") (pinfunction "PA13_25") (pintype "bidirectional"))
    )
    (net (code "30") (name "/SYNC_IN") (class "Default")
      (node (ref "MTi") (pin "16") (pinfunction "SYNC_IN_16") (pintype "input"))
      (node (ref "SI") (pin "0") (pinfunction "0_0") (pintype "passive"))
      (node (ref "U1") (pin "29") (pinfunction "PA15_29") (pintype "bidirectional"))
    )
    (net (code "31") (name "/SYNC_OUT") (class "Default")
      (node (ref "MTi") (pin "22") (pinfunction "DRDY_/_~{RE}_/_CTS_22") (pintype "output"))
      (node (ref "SO") (pin "0") (pinfunction "0_0") (pintype "passive"))
      (node (ref "U1") (pin "8") (pinfunction "PA01_8") (pintype "bidirectional"))
    )
    (net (code "32") (name "/TRACESWO") (class "Default")
      (node (ref "SWD") (pin "6") (pinfunction "SWO_6") (pintype "output"))
      (node (ref "U1") (pin "30") (pinfunction "PB03_30") (pintype "bidirectional"))
    )
    (net (code "33") (name "/UART_RX") (class "Default")
      (node (ref "MTi") (pin "23") (pinfunction "UART_RX_/_I2C_SCL_23") (pintype "input"))
      (node (ref "XRX") (pin "0") (pinfunction "0_0") (pintype "passive"))
    )
    (net (code "34") (name "/UART_TX") (class "Default")
      (node (ref "MTi") (pin "24") (pinfunction "UART_TX_/_I2C_SDA_24") (pintype "output"))
      (node (ref "XTX") (pin "0") (pinfunction "0_0") (pintype "passive"))
    )
    (net (code "35") (name "/USART1_DE") (class "Default")
      (node (ref "DE") (pin "0") (pinfunction "0_0") (pintype "passive"))
      (node (ref "U1") (pin "16") (pinfunction "PB01_16") (pintype "bidirectional"))
      (node (ref "U4") (pin "3") (pinfunction "DE_3") (pintype "input"))
    )
    (net (code "36") (name "/USART1_RE") (class "Default")
      (node (ref "RE") (pin "0") (pinfunction "0_0") (pintype "passive"))
      (node (ref "U1") (pin "15") (pinfunction "PB00_15") (pintype "bidirectional"))
      (node (ref "U4") (pin "2") (pinfunction "RE_2") (pintype "input"))
    )
    (net (code "37") (name "/USART1_RX") (class "Default")
      (node (ref "RX") (pin "0") (pinfunction "0_0") (pintype "passive"))
      (node (ref "U1") (pin "10") (pinfunction "PA03_10") (pintype "bidirectional"))
      (node (ref "U4") (pin "1") (pinfunction "RO_1") (pintype "output"))
    )
    (net (code "38") (name "/USART1_TX") (class "Default")
      (node (ref "TX") (pin "0") (pinfunction "0_0") (pintype "passive"))
      (node (ref "U1") (pin "9") (pinfunction "PA02_9") (pintype "bidirectional"))
      (node (ref "U4") (pin "4") (pinfunction "DI_4") (pintype "input"))
    )
    (net (code "39") (name "/VCC_RF") (class "Default")
      (node (ref "C23") (pin "2") (pinfunction "2_2") (pintype "passive"))
      (node (ref "U3") (pin "14") (pinfunction "VCC_RF_14") (pintype "power_in"))
      (node (ref "U9") (pin "1") (pinfunction "Vcc_1") (pintype "power_in"))
    )
    (net (code "40") (name "/WKUP") (class "Default")
      (node (ref "C17") (pin "2") (pinfunction "2_2") (pintype "passive"))
      (node (ref "R10") (pin "2") (pinfunction "2_2") (pintype "passive"))
      (node (ref "R9") (pin "1") (pinfunction "1_1") (pintype "passive"))
      (node (ref "U1") (pin "7") (pinfunction "PA00/WKUP_7") (pintype "bidirectional"))
      (node (ref "WKUP") (pin "0") (pinfunction "0_0") (pintype "passive"))
    )
    (net (code "41") (name "/XRST") (class "Default")
      (node (ref "MTi") (pin "6") (pinfunction "RST_6") (pintype "input"))
      (node (ref "R1") (pin "1") (pinfunction "1_1") (pintype "passive"))
      (node (ref "XRST") (pin "0") (pinfunction "0_0") (pintype "passive"))
    )
    (net (code "42") (name "3V3") (class "Default")
      (node (ref "3V3_1") (pin "0") (pinfunction "0_0") (pintype "passive"))
      (node (ref "3V3_2") (pin "0") (pinfunction "0_0") (pintype "passive"))
      (node (ref "BOOT") (pin "1") (pinfunction "1_1") (pintype "passive"))
      (node (ref "C10") (pin "2") (pinfunction "2_2") (pintype "passive"))
      (node (ref "C11") (pin "2") (pinfunction "2_2") (pintype "passive"))
      (node (ref "C12") (pin "2") (pinfunction "2_2") (pintype "passive"))
      (node (ref "C13") (pin "2") (pinfunction "2_2") (pintype "passive"))
      (node (ref "C17") (pin "1") (pinfunction "1_1") (pintype "passive"))
      (node (ref "C19") (pin "1") (pinfunction "1_1") (pintype "passive"))
      (node (ref "C21") (pin "2") (pinfunction "2_2") (pintype "passive"))
      (node (ref "C22") (pin "2") (pinfunction "2_2") (pintype "passive"))
      (node (ref "C3") (pin "2") (pinfunction "2_2") (pintype "passive"))
      (node (ref "C4") (pin "2") (pinfunction "2_2") (pintype "passive"))
      (node (ref "C9") (pin "2") (pinfunction "2_2") (pintype "passive"))
      (node (ref "L1") (pin "1") (pinfunction "1_1") (pintype "passive"))
      (node (ref "R11") (pin "2") (pinfunction "2_2") (pintype "passive"))
      (node (ref "R12") (pin "2") (pinfunction "2_2") (pintype "passive"))
      (node (ref "R3") (pin "2") (pinfunction "2_2") (pintype "passive"))
      (node (ref "R7") (pin "2") (pinfunction "2_2") (pintype "passive"))
      (node (ref "SWD") (pin "1") (pinfunction "VCC_1") (pintype "passive"))
      (node (ref "U1") (pin "1") (pinfunction "VCC_3_1") (pintype "power_in"))
      (node (ref "U1") (pin "19") (pinfunction "VCC_1_19") (pintype "power_in"))
      (node (ref "U1") (pin "27") (pinfunction "VCC_2_27") (pintype "power_in"))
      (node (ref "U2") (pin "1") (pinfunction "Mode_1") (pintype "input"))
      (node (ref "U2") (pin "3") (pinfunction "Vout_3") (pintype "power_in"))
      (node (ref "U2") (pin "4") (pinfunction "Vout_4") (pintype "power_in"))
      (node (ref "U4") (pin "8") (pinfunction "Vcc_8") (pintype "power_in"))
      (node (ref "U5") (pin "4") (pinfunction "VIN_4") (pintype "power_in"))
      (node (ref "U7") (pin "4") (pinfunction "VIN_4") (pintype "power_in"))
      (node (ref "U8") (pin "1") (pinfunction "Vdd_1") (pintype "power_in"))
      (node (ref "U8") (pin "4") (pinfunction "Vddio_4") (pintype "power_in"))
      (node (ref "WAKE") (pin "1") (pinfunction "1_1") (pintype "passive"))
    )
    (net (code "43") (name "3V3A") (class "Default")
      (node (ref "C7") (pin "2") (pinfunction "2_2") (pintype "passive"))
      (node (ref "C8") (pin "2") (pinfunction "2_2") (pintype "passive"))
      (node (ref "L1") (pin "2") (pinfunction "2_2") (pintype "passive"))
      (node (ref "U1") (pin "6") (pinfunction "VCCA_6") (pintype "power_in"))
    )
    (net (code "44") (name "3V3_GPS") (class "Default")
      (node (ref "C1") (pin "2") (pinfunction "2_2") (pintype "passive"))
      (node (ref "C14") (pin "1") (pinfunction "1_1") (pintype "passive"))
      (node (ref "C2") (pin "2") (pinfunction "2_2") (pintype "passive"))
      (node (ref "D2") (pin "1") (pinfunction "A_1") (pintype "passive"))
      (node (ref "G_3") (pin "0") (pinfunction "0_0") (pintype "passive"))
      (node (ref "U3") (pin "7") (pinfunction "VCC_IO_7") (pintype "power_in"))
      (node (ref "U3") (pin "8") (pinfunction "VCC_8") (pintype "power_in"))
      (node (ref "U5") (pin "2") (pinfunction "VOUT_2") (pintype "power_in"))
      (node (ref "U5") (pin "3") (pinfunction "VOUT_3") (pintype "power_in"))
    )
    (net (code "45") (name "3V3_GPS_VBKP") (class "Default")
      (node (ref "B1") (pin "+") (pinfunction "+_+") (pintype "power_in"))
      (node (ref "D2") (pin "2") (pinfunction "K_2") (pintype "passive"))
      (node (ref "G_B") (pin "0") (pinfunction "0_0") (pintype "passive"))
      (node (ref "U3") (pin "6") (pinfunction "V_BCKP_6") (pintype "power_in"))
    )
    (net (code "46") (name "3V3_L1") (class "Default")
      (node (ref "C16") (pin "1") (pinfunction "1_1") (pintype "passive"))
      (node (ref "L13") (pin "0") (pinfunction "0_0") (pintype "passive"))
      (node (ref "MTi") (pin "5") (pinfunction "VCC_5") (pintype "power_in"))
      (node (ref "MTi") (pin "7") (pinfunction "VCCIO_7") (pintype "power_in"))
      (node (ref "R1") (pin "2") (pinfunction "2_2") (pintype "passive"))
      (node (ref "U7") (pin "2") (pinfunction "VOUT_2") (pintype "power_in"))
      (node (ref "U7") (pin "3") (pinfunction "VOUT_3") (pintype "power_in"))
    )
    (net (code "47") (name "5V0") (class "Default")
      (node (ref "5V0") (pin "0") (pinfunction "0_0") (pintype "passive"))
      (node (ref "Q1") (pin "2") (pinfunction "S_2") (pintype "passive"))
      (node (ref "U2") (pin "5") (pinfunction "EN_5") (pintype "input"))
      (node (ref "U2") (pin "7") (pinfunction "Vin_7") (pintype "power_in"))
      (node (ref "U2") (pin "8") (pinfunction "Vin_8") (pintype "power_in"))
    )
    (net (code "49") (name "GND") (class "Default")
      (node (ref "B1") (pin "-") (pinfunction "-_-") (pintype "power_in"))
      (node (ref "C1") (pin "1") (pinfunction "1_1") (pintype "passive"))
      (node (ref "C10") (pin "1") (pinfunction "1_1") (pintype "passive"))
      (node (ref "C11") (pin "1") (pinfunction "1_1") (pintype "passive"))
      (node (ref "C12") (pin "1") (pinfunction "1_1") (pintype "passive"))
      (node (ref "C13") (pin "1") (pinfunction "1_1") (pintype "passive"))
      (node (ref "C18") (pin "1") (pinfunction "1_1") (pintype "passive"))
      (node (ref "C2") (pin "1") (pinfunction "1_1") (pintype "passive"))
      (node (ref "C20") (pin "2") (pinfunction "2_2") (pintype "passive"))
      (node (ref "C21") (pin "1") (pinfunction "1_1") (pintype "passive"))
      (node (ref "C22") (pin "1") (pinfunction "1_1") (pintype "passive"))
      (node (ref "C3") (pin "1") (pinfunction "1_1") (pintype "passive"))
      (node (ref "C4") (pin "1") (pinfunction "1_1") (pintype "passive"))
      (node (ref "C5") (pin "1") (pinfunction "1_1") (pintype "passive"))
      (node (ref "C6") (pin "1") (pinfunction "1_1") (pintype "passive"))
      (node (ref "C7") (pin "1") (pinfunction "1_1") (pintype "passive"))
      (node (ref "C8") (pin "1") (pinfunction "1_1") (pintype "passive"))
      (node (ref "C9") (pin "1") (pinfunction "1_1") (pintype "passive"))
      (node (ref "GND") (pin "0") (pinfunction "0_0") (pintype "passive"))
      (node (ref "J3") (pin "1") (pinfunction "1_1") (pintype "passive"))
      (node (ref "MTi") (pin "13") (pinfunction "GND_13") (pintype "power_in"))
      (node (ref "MTi") (pin "25") (pinfunction "GND_25") (pintype "power_in"))
      (node (ref "MTi") (pin "4") (pinfunction "GND_4") (pintype "power_in"))
      (node (ref "MTi") (pin "8") (pinfunction "GND_8") (pintype "power_in"))
      (node (ref "R10") (pin "1") (pinfunction "1_1") (pintype "passive"))
      (node (ref "R13") (pin "2") (pinfunction "2_2") (pintype "passive"))
      (node (ref "R15") (pin "1") (pinfunction "1_1") (pintype "passive"))
      (node (ref "R16") (pin "2") (pinfunction "2_2") (pintype "passive"))
      (node (ref "R17") (pin "1") (pinfunction "1_1") (pintype "passive"))
      (node (ref "R18") (pin "1") (pinfunction "1_1") (pintype "passive"))
      (node (ref "R2") (pin "1") (pinfunction "1_1") (pintype "passive"))
      (node (ref "R4") (pin "1") (pinfunction "1_1") (pintype "passive"))
      (node (ref "R5") (pin "1") (pinfunction "1_1") (pintype "passive"))
      (node (ref "R6") (pin "1") (pinfunction "1_1") (pintype "passive"))
      (node (ref "R8") (pin "1") (pinfunction "1_1") (pintype "passive"))
      (node (ref "RST") (pin "1") (pinfunction "1_1") (pintype "passive"))
      (node (ref "SWD") (pin "3") (pinfunction "GND_3") (pintype "passive"))
      (node (ref "SWD") (pin "5") (pinfunction "GND_5") (pintype "passive"))
      (node (ref "SWD") (pin "9") (pinfunction "GNDDET_9") (pintype "passive"))
      (node (ref "U1") (pin "18") (pinfunction "GND_1_18") (pintype "power_in"))
      (node (ref "U1") (pin "26") (pinfunction "GND_2_26") (pintype "power_in"))
      (node (ref "U1") (pin "36") (pinfunction "GND_3_36") (pintype "power_in"))
      (node (ref "U1") (pin "5") (pinfunction "GNDA_5") (pintype "power_in"))
      (node (ref "U2") (pin "2") (pinfunction "GND_2") (pintype "power_in"))
      (node (ref "U2") (pin "6") (pinfunction "GND_6") (pintype "power_in"))
      (node (ref "U2") (pin "9") (pinfunction "GND_9") (pintype "power_in"))
      (node (ref "U3") (pin "1") (pinfunction "GND_1") (pintype "power_in"))
      (node (ref "U4") (pin "5") (pinfunction "GND_5") (pintype "power_in"))
      (node (ref "U8") (pin "3") (pinfunction "GND_3") (pintype "power_in"))
      (node (ref "X1") (pin "2") (pinfunction "2_2") (pintype "power_in"))
      (node (ref "X1") (pin "4") (pinfunction "4_4") (pintype "power_in"))
    )
    (net (code "50") (name "GND_RF") (class "Default")
      (node (ref "Antenna") (pin "GND") (pinfunction "GND_GND") (pintype "passive"))
      (node (ref "C23") (pin "1") (pinfunction "1_1") (pintype "passive"))
      (node (ref "L3") (pin "1") (pinfunction "1_1") (pintype "passive"))
      (node (ref "U3") (pin "10") (pinfunction "GND_10") (pintype "power_in"))
      (node (ref "U3") (pin "12") (pinfunction "GND_12") (pintype "power_in"))
      (node (ref "U9") (pin "7") (pinfunction "GND_7") (pintype "power_in"))
    )
    (net (code "51") (name "Net-(BOOT-Pad2)") (class "Default")
      (node (ref "BOOT") (pin "2") (pinfunction "2_2") (pintype "passive"))
      (node (ref "R14") (pin "2") (pinfunction "2_2") (pintype "passive"))
    )
    (net (code "52") (name "Net-(D1-PadK)") (class "Default")
      (node (ref "D1") (pin "K") (pinfunction "K_K") (pintype "power_in"))
      (node (ref "R13") (pin "1") (pinfunction "1_1") (pintype "passive"))
    )
    (net (code "53") (name "Net-(Q1-G)") (class "Default")
      (node (ref "Q1") (pin "1") (pinfunction "G_1") (pintype "passive"))
      (node (ref "R2") (pin "2") (pinfunction "2_2") (pintype "passive"))
    )
    (net (code "54") (name "Net-(R9-Pad2)") (class "Default")
      (node (ref "R9") (pin "2") (pinfunction "2_2") (pintype "passive"))
      (node (ref "WAKE") (pin "2") (pinfunction "2_2") (pintype "passive"))
    )
    (net (code "55") (name "Net-(U5-R1{slash}C1)") (class "Default")
      (node (ref "C14") (pin "2") (pinfunction "2_2") (pintype "passive"))
      (node (ref "R3") (pin "1") (pinfunction "1_1") (pintype "passive"))
      (node (ref "U5") (pin "6") (pinfunction "R1/C1_6") (pintype "input"))
    )
    (net (code "56") (name "Net-(U5-R2)") (class "Default")
      (node (ref "R4") (pin "2") (pinfunction "2_2") (pintype "passive"))
      (node (ref "U5") (pin "1") (pinfunction "R2_1") (pintype "input"))
    )
    (net (code "57") (name "Net-(U7-R1{slash}C1)") (class "Default")
      (node (ref "C16") (pin "2") (pinfunction "2_2") (pintype "passive"))
      (node (ref "R7") (pin "1") (pinfunction "1_1") (pintype "passive"))
      (node (ref "U7") (pin "6") (pinfunction "R1/C1_6") (pintype "input"))
    )
    (net (code "58") (name "Net-(U7-R2)") (class "Default")
      (node (ref "R8") (pin "2") (pinfunction "2_2") (pintype "passive"))
      (node (ref "U7") (pin "1") (pinfunction "R2_1") (pintype "input"))
    )
    (net (code "59") (name "Net-(U8-CAP)") (class "Default")
      (node (ref "C20") (pin "1") (pinfunction "1_1") (pintype "passive"))
      (node (ref "U8") (pin "2") (pinfunction "CAP_2") (pintype "passive"))
    )
    (net (code "60") (name "Net-(U9-AI)") (class "Default")
      (node (ref "L2") (pin "2") (pinfunction "2_2") (pintype "passive"))
      (node (ref "U9") (pin "5") (pinfunction "AI_5") (pintype "input"))
    )
    (net (code "61") (name "Net-(U9-SO)") (class "Default")
      (node (ref "L2") (pin "1") (pinfunction "1_1") (pintype "passive"))
      (node (ref "U9") (pin "4") (pinfunction "SO_4") (pintype "output"))
    )
    (net (code "62") (name "VIN") (class "Default")
      (node (ref "J3") (pin "2") (pinfunction "2_2") (pintype "passive"))
      (node (ref "Q1") (pin "3") (pinfunction "D_3") (pintype "passive"))
      (node (ref "Vin") (pin "0") (pinfunction "0_0") (pintype "passive"))
    )
    (net (code "63") (name "unconnected-(F1-Fiducial_1mm-Pad1)") (class "Default")
      (node (ref "F1") (pin "1") (pinfunction "Fiducial_1mm_1") (pintype "passive"))
    )
    (net (code "64") (name "unconnected-(F2-Fiducial_1mm-Pad1)") (class "Default")
      (node (ref "F2") (pin "1") (pinfunction "Fiducial_1mm_1") (pintype "passive"))
    )
    (net (code "65") (name "unconnected-(F3-Fiducial_1mm-Pad1)") (class "Default")
      (node (ref "F3") (pin "1") (pinfunction "Fiducial_1mm_1") (pintype "passive"))
    )
    (net (code "66") (name "unconnected-(F4-Fiducial_1mm-Pad1)") (class "Default")
      (node (ref "F4") (pin "1") (pinfunction "Fiducial_1mm_1") (pintype "passive"))
    )
    (net (code "67") (name "unconnected-(U1B-Thermal-Pad37)") (class "Default")
      (node (ref "U1") (pin "37") (pinfunction "Thermal_37") (pintype "power_in"))
    )
    (net (code "68") (name "unconnected-(U3-RESET_N-Pad9)") (class "Default")
      (node (ref "U3") (pin "9") (pinfunction "RESET_N_9") (pintype "input"))
    )
    (net (code "69") (name "unconnected-(U3-Reserved-Pad18)") (class "Default")
      (node (ref "U3") (pin "18") (pinfunction "Reserved_18") (pintype "passive"))
    )
    (net (code "70") (name "unconnected-(U3-SCL-Pad17)") (class "Default")
      (node (ref "U3") (pin "17") (pinfunction "SCL_17") (pintype "input"))
    )
    (net (code "71") (name "unconnected-(U3-SDA-Pad16)") (class "Default")
      (node (ref "U3") (pin "16") (pinfunction "SDA_16") (pintype "bidirectional"))
    )
    (net (code "72") (name "unconnected-(U3-V_ANT-Pad15)") (class "Default")
      (node (ref "U3") (pin "15") (pinfunction "V_ANT_15") (pintype "power_in"))
    )
    (net (code "73") (name "unconnected-(U8-INT1-Pad6)") (class "Default")
      (node (ref "U8") (pin "6") (pinfunction "INT1_6") (pintype "output"))
    )
    (net (code "74") (name "unconnected-(U8-INT2-Pad5)") (class "Default")
      (node (ref "U8") (pin "5") (pinfunction "INT2_5") (pintype "output"))
    )
  )
)
